# easyEDA_proj_file.net
KiCad netlist of a schematic drawn in EasyEDA
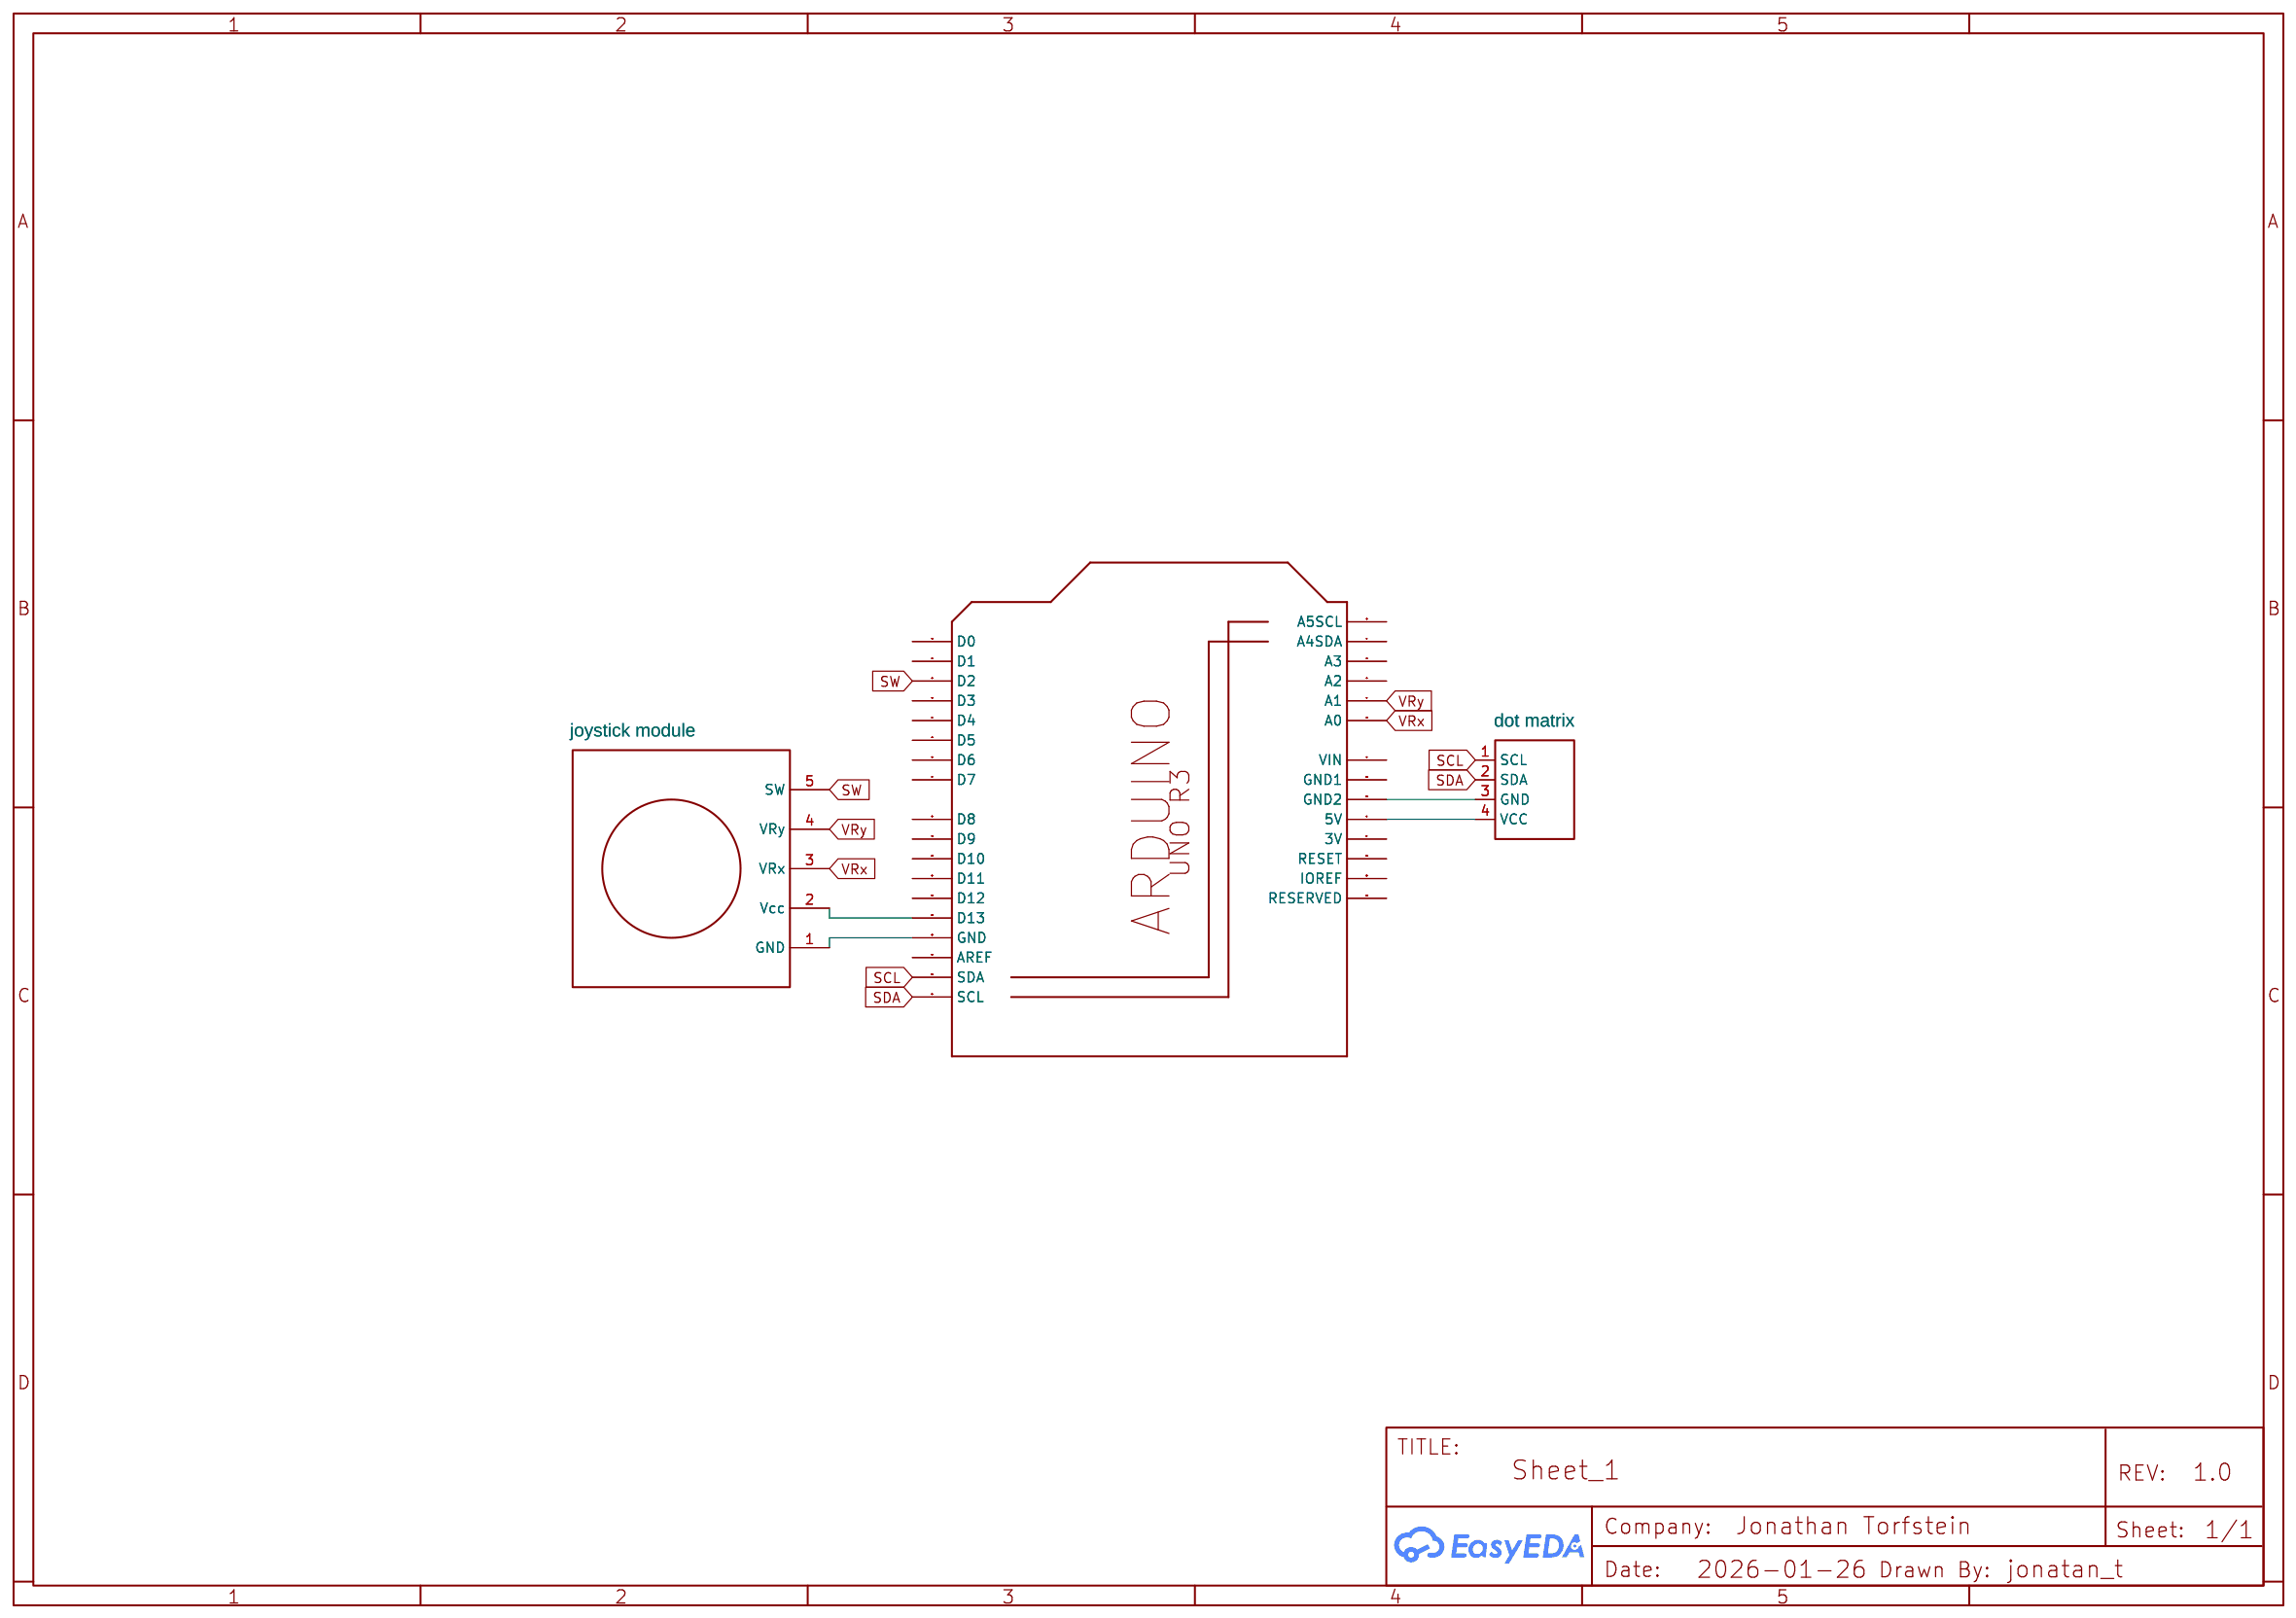
[diagram p0: schematic sheet]

(export (version "E")
  (design (tool "Eeschema 10.0.6"))
  (components
    (comp (ref "U1") (value "ARDUINOR3-DIMENSION") (libsource (lib "") (part "ARDUINOR3-DIMENSION")))
    (comp (ref "U2")
      (value "dot matrix")
      (fields
        (field (name "Manufacturer Part") "350424-1")
        (field (name "Manufacturer") "TE Connectivity(泰科电子)")
      )
      (libsource (lib "") (part "350424-1"))
    )
    (comp (ref "U3") (value "joystick module") (libsource (lib "") (part "HW-504JOYSTICK")))
  )
  (nets
    (net (code "1") (name "Net-(U2-GND)") (class "Default")
      (node (ref "U1") (pin "GND2") (pinfunction "GND2_GND2") (pintype "passive"))
      (node (ref "U2") (pin "3") (pinfunction "GND_3") (pintype "unspecified"))
    )
    (net (code "2") (name "Net-(U2-VCC)") (class "Default")
      (node (ref "U1") (pin "5V") (pinfunction "5V_5V") (pintype "passive"))
      (node (ref "U2") (pin "4") (pinfunction "VCC_4") (pintype "unspecified"))
    )
    (net (code "3") (name "Net-(U3-GND)") (class "Default")
      (node (ref "U1") (pin "GND") (pinfunction "GND_GND") (pintype "passive"))
      (node (ref "U3") (pin "1") (pinfunction "GND_1") (pintype "unspecified"))
    )
    (net (code "4") (name "Net-(U3-Vcc)") (class "Default")
      (node (ref "U1") (pin "D13") (pinfunction "D13_D13") (pintype "unspecified"))
      (node (ref "U3") (pin "2") (pinfunction "Vcc_2") (pintype "unspecified"))
    )
    (net (code "5") (name "SCL") (class "Default")
      (node (ref "U1") (pin "SDA") (pinfunction "SDA_SDA") (pintype "unspecified"))
      (node (ref "U2") (pin "1") (pinfunction "SCL_1") (pintype "unspecified"))
    )
    (net (code "6") (name "SDA") (class "Default")
      (node (ref "U1") (pin "SCL") (pinfunction "SCL_SCL") (pintype "unspecified"))
      (node (ref "U2") (pin "2") (pinfunction "SDA_2") (pintype "unspecified"))
    )
    (net (code "7") (name "SW") (class "Default")
      (node (ref "U1") (pin "D2") (pinfunction "D2_D2") (pintype "unspecified"))
      (node (ref "U3") (pin "5") (pinfunction "SW_5") (pintype "unspecified"))
    )
    (net (code "8") (name "VRx") (class "Default")
      (node (ref "U1") (pin "A0") (pinfunction "A0_A0") (pintype "unspecified"))
      (node (ref "U3") (pin "3") (pinfunction "VRx_3") (pintype "unspecified"))
    )
    (net (code "9") (name "VRy") (class "Default")
      (node (ref "U1") (pin "A1") (pinfunction "A1_A1") (pintype "unspecified"))
      (node (ref "U3") (pin "4") (pinfunction "VRy_4") (pintype "unspecified"))
    )
    (net (code "10") (name "unconnected-(U1-A4SDA-PadA4)") (class "Default")
      (node (ref "U1") (pin "A4") (pinfunction "A4SDA_A4") (pintype "unspecified"))
    )
    (net (code "11") (name "unconnected-(U1-A5SCL-PadA5)") (class "Default")
      (node (ref "U1") (pin "A5") (pinfunction "A5SCL_A5") (pintype "unspecified"))
    )
    (net (code "12") (name "unconnected-(U1-Pad3V)") (class "Default")
      (node (ref "U1") (pin "3V") (pinfunction "3V_3V") (pintype "passive"))
    )
    (net (code "13") (name "unconnected-(U1-PadA2)") (class "Default")
      (node (ref "U1") (pin "A2") (pinfunction "A2_A2") (pintype "unspecified"))
    )
    (net (code "14") (name "unconnected-(U1-PadA3)") (class "Default")
      (node (ref "U1") (pin "A3") (pinfunction "A3_A3") (pintype "unspecified"))
    )
    (net (code "15") (name "unconnected-(U1-PadAREF)") (class "Default")
      (node (ref "U1") (pin "AREF") (pinfunction "AREF_AREF") (pintype "unspecified"))
    )
    (net (code "16") (name "unconnected-(U1-PadD0)") (class "Default")
      (node (ref "U1") (pin "D0") (pinfunction "D0_D0") (pintype "unspecified"))
    )
    (net (code "17") (name "unconnected-(U1-PadD1)") (class "Default")
      (node (ref "U1") (pin "D1") (pinfunction "D1_D1") (pintype "unspecified"))
    )
    (net (code "18") (name "unconnected-(U1-PadD3)") (class "Default")
      (node (ref "U1") (pin "D3") (pinfunction "D3_D3") (pintype "unspecified"))
    )
    (net (code "19") (name "unconnected-(U1-PadD4)") (class "Default")
      (node (ref "U1") (pin "D4") (pinfunction "D4_D4") (pintype "unspecified"))
    )
    (net (code "20") (name "unconnected-(U1-PadD5)") (class "Default")
      (node (ref "U1") (pin "D5") (pinfunction "D5_D5") (pintype "unspecified"))
    )
    (net (code "21") (name "unconnected-(U1-PadD6)") (class "Default")
      (node (ref "U1") (pin "D6") (pinfunction "D6_D6") (pintype "unspecified"))
    )
    (net (code "22") (name "unconnected-(U1-PadD7)") (class "Default")
      (node (ref "U1") (pin "D7") (pinfunction "D7_D7") (pintype "unspecified"))
    )
    (net (code "23") (name "unconnected-(U1-PadD8)") (class "Default")
      (node (ref "U1") (pin "D8") (pinfunction "D8_D8") (pintype "unspecified"))
    )
    (net (code "24") (name "unconnected-(U1-PadD9)") (class "Default")
      (node (ref "U1") (pin "D9") (pinfunction "D9_D9") (pintype "unspecified"))
    )
    (net (code "25") (name "unconnected-(U1-PadD10)") (class "Default")
      (node (ref "U1") (pin "D10") (pinfunction "D10_D10") (pintype "unspecified"))
    )
    (net (code "26") (name "unconnected-(U1-PadD11)") (class "Default")
      (node (ref "U1") (pin "D11") (pinfunction "D11_D11") (pintype "unspecified"))
    )
    (net (code "27") (name "unconnected-(U1-PadD12)") (class "Default")
      (node (ref "U1") (pin "D12") (pinfunction "D12_D12") (pintype "unspecified"))
    )
    (net (code "28") (name "unconnected-(U1-PadGND1)") (class "Default")
      (node (ref "U1") (pin "GND1") (pinfunction "GND1_GND1") (pintype "passive"))
    )
    (net (code "29") (name "unconnected-(U1-PadIOREF)") (class "Default")
      (node (ref "U1") (pin "IOREF") (pinfunction "IOREF_IOREF") (pintype "output"))
    )
    (net (code "30") (name "unconnected-(U1-PadRESERVED)") (class "Default")
      (node (ref "U1") (pin "RESERVED") (pinfunction "RESERVED_RESERVED") (pintype "unspecified"))
    )
    (net (code "31") (name "unconnected-(U1-PadRESET)") (class "Default")
      (node (ref "U1") (pin "RESET") (pinfunction "RESET_RESET") (pintype "unspecified"))
    )
    (net (code "32") (name "unconnected-(U1-PadVIN)") (class "Default")
      (node (ref "U1") (pin "VIN") (pinfunction "VIN_VIN") (pintype "passive"))
    )
  )
)
